# esp32.net
KiCad netlist of a schematic drawn in Altium Designer
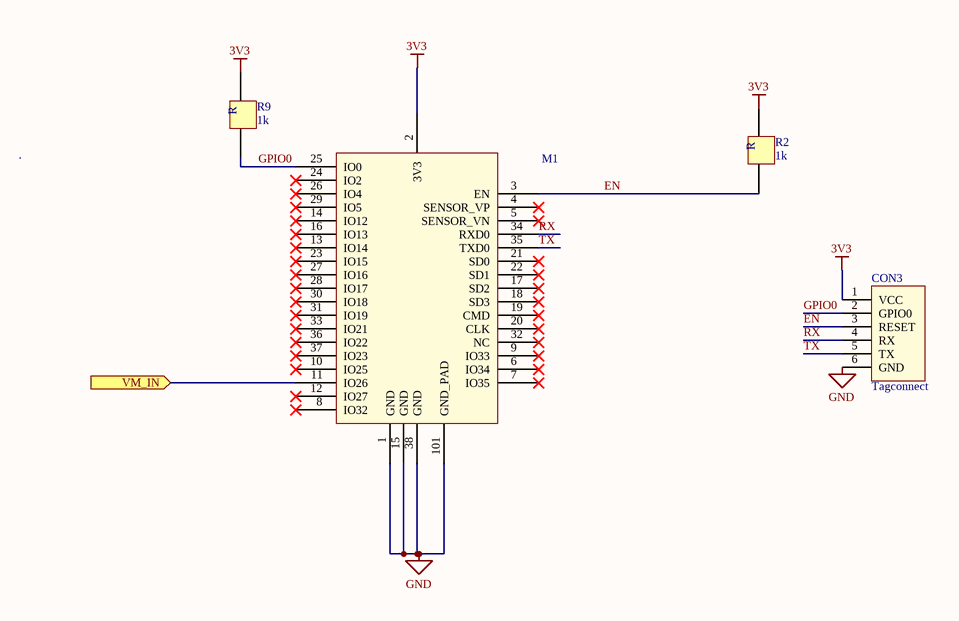
[diagram p0: esp32.SchDoc]

(export (version "E")
  (design (tool "Eeschema 10.0.6"))
  (components
    (comp (ref "CON3")
      (value "Tagconnect")
      (footprint "Tagconnect")
      (libsource (lib "conector's_and_TP") (part "Tagconnect"))
    )
    (comp (ref "M1")
      (value "ESP32S_Module")
      (footprint "ESP32S_W")
      (description "Esp-32S")
      (libsource (lib "ESPS") (part "ESP32S_Module"))
    )
    (comp (ref "R2") (value "1k") (footprint "0603") (libsource (lib "pasives") (part "resistor")))
    (comp (ref "R9") (value "1k") (footprint "0603") (libsource (lib "pasives") (part "resistor")))
  )
  (nets
    (net (code "1") (name "/EN") (class "Default")
      (node (ref "CON3") (pin "3") (pinfunction "RESET_3") (pintype "passive"))
      (node (ref "M1") (pin "3") (pinfunction "EN_3") (pintype "power_in"))
      (node (ref "R2") (pin "2") (pinfunction "2_2") (pintype "passive"))
    )
    (net (code "2") (name "/GPIO0") (class "Default")
      (node (ref "CON3") (pin "2") (pinfunction "GPIO0_2") (pintype "passive"))
      (node (ref "M1") (pin "25") (pinfunction "IO0_25") (pintype "passive"))
      (node (ref "R9") (pin "2") (pinfunction "2_2") (pintype "passive"))
    )
    (net (code "3") (name "/RX") (class "Default")
      (node (ref "CON3") (pin "4") (pinfunction "RX_4") (pintype "passive"))
      (node (ref "M1") (pin "34") (pinfunction "RXD0_34") (pintype "passive"))
    )
    (net (code "4") (name "/TX") (class "Default")
      (node (ref "CON3") (pin "5") (pinfunction "TX_5") (pintype "passive"))
      (node (ref "M1") (pin "35") (pinfunction "TXD0_35") (pintype "passive"))
    )
    (net (code "5") (name "/VM_IN") (class "Default")
      (node (ref "M1") (pin "11") (pinfunction "IO26_11") (pintype "passive"))
    )
    (net (code "6") (name "3V3") (class "Default")
      (node (ref "CON3") (pin "1") (pinfunction "VCC_1") (pintype "passive"))
      (node (ref "M1") (pin "2") (pinfunction "3V3_2") (pintype "power_in"))
      (node (ref "R2") (pin "1") (pinfunction "1_1") (pintype "passive"))
      (node (ref "R9") (pin "1") (pinfunction "1_1") (pintype "passive"))
    )
    (net (code "7") (name "GND") (class "Default")
      (node (ref "CON3") (pin "6") (pinfunction "GND_6") (pintype "passive"))
      (node (ref "M1") (pin "1") (pinfunction "GND_1") (pintype "power_in"))
      (node (ref "M1") (pin "101") (pinfunction "GND_PAD_101") (pintype "power_in"))
      (node (ref "M1") (pin "15") (pinfunction "GND_15") (pintype "power_in"))
      (node (ref "M1") (pin "38") (pinfunction "GND_38") (pintype "power_in"))
    )
    (net (code "8") (name "unconnected-(M1-CLK-Pad20)") (class "Default")
      (node (ref "M1") (pin "20") (pinfunction "CLK_20") (pintype "passive+no_connect"))
    )
    (net (code "9") (name "unconnected-(M1-CMD-Pad19)") (class "Default")
      (node (ref "M1") (pin "19") (pinfunction "CMD_19") (pintype "passive+no_connect"))
    )
    (net (code "10") (name "unconnected-(M1-IO2-Pad24)") (class "Default")
      (node (ref "M1") (pin "24") (pinfunction "IO2_24") (pintype "passive+no_connect"))
    )
    (net (code "11") (name "unconnected-(M1-IO4-Pad26)") (class "Default")
      (node (ref "M1") (pin "26") (pinfunction "IO4_26") (pintype "passive+no_connect"))
    )
    (net (code "12") (name "unconnected-(M1-IO5-Pad29)") (class "Default")
      (node (ref "M1") (pin "29") (pinfunction "IO5_29") (pintype "passive+no_connect"))
    )
    (net (code "13") (name "unconnected-(M1-IO12-Pad14)") (class "Default")
      (node (ref "M1") (pin "14") (pinfunction "IO12_14") (pintype "passive+no_connect"))
    )
    (net (code "14") (name "unconnected-(M1-IO13-Pad16)") (class "Default")
      (node (ref "M1") (pin "16") (pinfunction "IO13_16") (pintype "passive+no_connect"))
    )
    (net (code "15") (name "unconnected-(M1-IO14-Pad13)") (class "Default")
      (node (ref "M1") (pin "13") (pinfunction "IO14_13") (pintype "passive+no_connect"))
    )
    (net (code "16") (name "unconnected-(M1-IO15-Pad23)") (class "Default")
      (node (ref "M1") (pin "23") (pinfunction "IO15_23") (pintype "passive+no_connect"))
    )
    (net (code "17") (name "unconnected-(M1-IO16-Pad27)") (class "Default")
      (node (ref "M1") (pin "27") (pinfunction "IO16_27") (pintype "passive+no_connect"))
    )
    (net (code "18") (name "unconnected-(M1-IO17-Pad28)") (class "Default")
      (node (ref "M1") (pin "28") (pinfunction "IO17_28") (pintype "passive+no_connect"))
    )
    (net (code "19") (name "unconnected-(M1-IO18-Pad30)") (class "Default")
      (node (ref "M1") (pin "30") (pinfunction "IO18_30") (pintype "passive+no_connect"))
    )
    (net (code "20") (name "unconnected-(M1-IO19-Pad31)") (class "Default")
      (node (ref "M1") (pin "31") (pinfunction "IO19_31") (pintype "passive+no_connect"))
    )
    (net (code "21") (name "unconnected-(M1-IO21-Pad33)") (class "Default")
      (node (ref "M1") (pin "33") (pinfunction "IO21_33") (pintype "passive+no_connect"))
    )
    (net (code "22") (name "unconnected-(M1-IO22-Pad36)") (class "Default")
      (node (ref "M1") (pin "36") (pinfunction "IO22_36") (pintype "passive+no_connect"))
    )
    (net (code "23") (name "unconnected-(M1-IO23-Pad37)") (class "Default")
      (node (ref "M1") (pin "37") (pinfunction "IO23_37") (pintype "passive+no_connect"))
    )
    (net (code "24") (name "unconnected-(M1-IO25-Pad10)") (class "Default")
      (node (ref "M1") (pin "10") (pinfunction "IO25_10") (pintype "passive+no_connect"))
    )
    (net (code "25") (name "unconnected-(M1-IO27-Pad12)") (class "Default")
      (node (ref "M1") (pin "12") (pinfunction "IO27_12") (pintype "passive+no_connect"))
    )
    (net (code "26") (name "unconnected-(M1-IO32-Pad8)") (class "Default")
      (node (ref "M1") (pin "8") (pinfunction "IO32_8") (pintype "passive+no_connect"))
    )
    (net (code "27") (name "unconnected-(M1-IO33-Pad9)") (class "Default")
      (node (ref "M1") (pin "9") (pinfunction "IO33_9") (pintype "passive+no_connect"))
    )
    (net (code "28") (name "unconnected-(M1-IO34-Pad6)") (class "Default")
      (node (ref "M1") (pin "6") (pinfunction "IO34_6") (pintype "passive+no_connect"))
    )
    (net (code "29") (name "unconnected-(M1-IO35-Pad7)") (class "Default")
      (node (ref "M1") (pin "7") (pinfunction "IO35_7") (pintype "passive+no_connect"))
    )
    (net (code "30") (name "unconnected-(M1-NC-Pad32)") (class "Default")
      (node (ref "M1") (pin "32") (pinfunction "NC_32") (pintype "passive+no_connect"))
    )
    (net (code "31") (name "unconnected-(M1-SD0-Pad21)") (class "Default")
      (node (ref "M1") (pin "21") (pinfunction "SD0_21") (pintype "passive+no_connect"))
    )
    (net (code "32") (name "unconnected-(M1-SD1-Pad22)") (class "Default")
      (node (ref "M1") (pin "22") (pinfunction "SD1_22") (pintype "passive+no_connect"))
    )
    (net (code "33") (name "unconnected-(M1-SD2-Pad17)") (class "Default")
      (node (ref "M1") (pin "17") (pinfunction "SD2_17") (pintype "passive+no_connect"))
    )
    (net (code "34") (name "unconnected-(M1-SD3-Pad18)") (class "Default")
      (node (ref "M1") (pin "18") (pinfunction "SD3_18") (pintype "passive+no_connect"))
    )
    (net (code "35") (name "unconnected-(M1-SENSOR_VN-Pad5)") (class "Default")
      (node (ref "M1") (pin "5") (pinfunction "SENSOR_VN_5") (pintype "passive+no_connect"))
    )
    (net (code "36") (name "unconnected-(M1-SENSOR_VP-Pad4)") (class "Default")
      (node (ref "M1") (pin "4") (pinfunction "SENSOR_VP_4") (pintype "passive+no_connect"))
    )
  )
)
